# PW_SUPPLY.net
KiCad netlist of a schematic drawn in Altium Designer
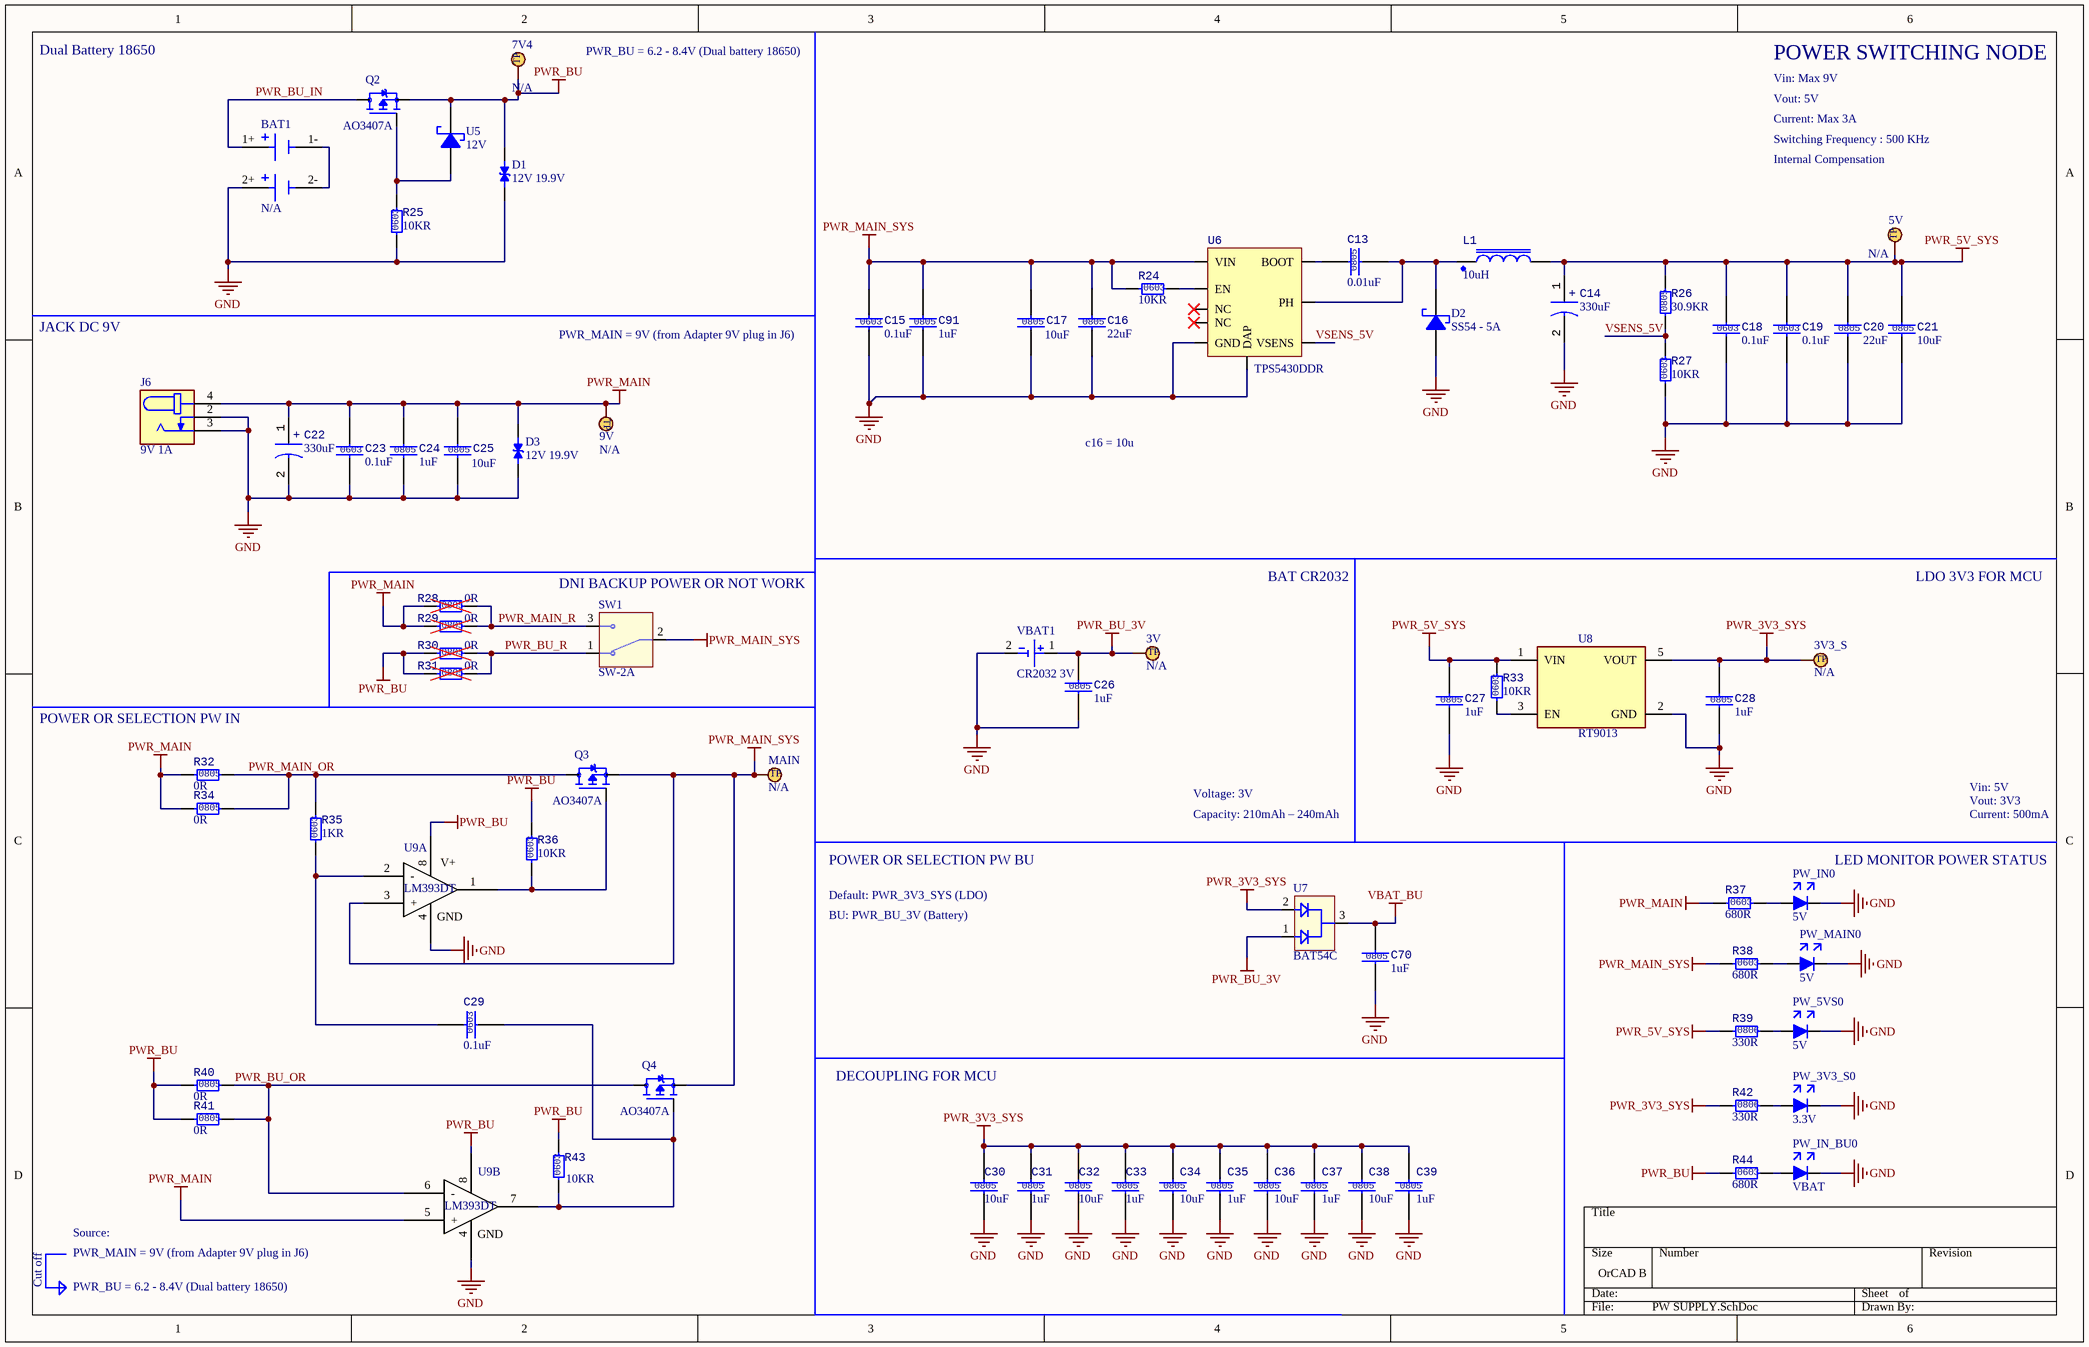
[diagram p0: PW SUPPLY.SchDoc]

(export (version "E")
  (design (tool "Eeschema 10.0.6"))
  (components
    (comp (ref "3V")
      (value "N/A")
      (footprint "Test_point")
      (fields (field (name "Comment") "TEST_POINT"))
      (libsource (lib "Database_Libs1") (part "Test_point"))
    )
    (comp (ref "3V3_S")
      (value "N/A")
      (footprint "Test_point")
      (fields (field (name "Comment") "TEST_POINT"))
      (libsource (lib "Database_Libs1") (part "Test_point"))
    )
    (comp (ref "5V")
      (value "N/A")
      (footprint "Test_point")
      (fields (field (name "Comment") "TEST_POINT"))
      (libsource (lib "Database_Libs1") (part "Test_point"))
    )
    (comp (ref "7V4")
      (value "N/A")
      (footprint "Test_point")
      (fields (field (name "Comment") "TEST_POINT"))
      (libsource (lib "Database_Libs1") (part "Test_point"))
    )
    (comp (ref "9V")
      (value "N/A")
      (footprint "Test_point")
      (fields (field (name "Comment") "TEST_POINT"))
      (libsource (lib "Database_Libs1") (part "Test_point"))
    )
    (comp (ref "BAT1")
      (value "N/A")
      (footprint "Dual_BAT_PCB")
      (description "Dual_Battery_Case_18650")
      (fields (field (name "Comment") "Dual_Battery_Case"))
      (libsource (lib "Database_Libs1") (part "Dual_BAT"))
    )
    (comp (ref "C13")
      (value "0.01uF")
      (footprint "CAPCER 0805 SMD")
      (description "CAPACITOR SMD 0.01uF 50V 10% 0805")
      (fields (field (name "SIZE") "0805") (field (name "TOLERANCE") "10%"))
      (libsource (lib "Database_Libs1") (part "CAPACITOR"))
    )
    (comp (ref "C14")
      (value "330uF")
      (footprint "CAP ALU 6377")
      (description "CAPACITOR ALU SMD 220uF 6.3V 20% 6377")
      (fields (field (name "TOLERANCE") "20%"))
      (libsource (lib "Database_Libs1") (part "CAPACITOR ALU"))
    )
    (comp (ref "C15")
      (value "0.1uF")
      (footprint "CAPCER 0805 SMD")
      (description "CAPACITOR SMD 0.1uF 50V 10% 0603")
      (fields (field (name "SIZE") "0603") (field (name "TOLERANCE") "10%"))
      (libsource (lib "Database_Libs1") (part "CAPACITOR"))
    )
    (comp (ref "C16")
      (value "22uF")
      (footprint "CAPCER 0805 SMD")
      (description "CAPACITOR SMD 22uF 50V 10% 0805")
      (fields (field (name "SIZE") "0805") (field (name "TOLERANCE") "10%"))
      (libsource (lib "Database_Libs1") (part "CAPACITOR"))
    )
    (comp (ref "C17")
      (value "10uF")
      (footprint "CAPCER 0603 SMD")
      (description "CAPACITOR SMD 10uF 25V 10% 0805")
      (fields (field (name "SIZE") "0805") (field (name "TOLERANCE") "10%"))
      (libsource (lib "Database_Libs1") (part "CAPACITOR"))
    )
    (comp (ref "C18")
      (value "0.1uF")
      (footprint "CAPCER 0805 SMD")
      (description "CAPACITOR SMD 0.1uF 50V 10% 0603")
      (fields (field (name "SIZE") "0603") (field (name "TOLERANCE") "10%"))
      (libsource (lib "Database_Libs1") (part "CAPACITOR"))
    )
    (comp (ref "C19")
      (value "0.1uF")
      (footprint "CAPCER 0805 SMD")
      (description "CAPACITOR SMD 0.1uF 50V 10% 0603")
      (fields (field (name "SIZE") "0603") (field (name "TOLERANCE") "10%"))
      (libsource (lib "Database_Libs1") (part "CAPACITOR"))
    )
    (comp (ref "C20")
      (value "22uF")
      (footprint "CAPCER 0805 SMD")
      (description "CAPACITOR SMD 22uF 50V 10% 0805")
      (fields (field (name "SIZE") "0805") (field (name "TOLERANCE") "10%"))
      (libsource (lib "Database_Libs1") (part "CAPACITOR"))
    )
    (comp (ref "C21")
      (value "10uF")
      (footprint "CAPCER 0603 SMD")
      (description "CAPACITOR SMD 10uF 25V 10% 0805")
      (fields (field (name "SIZE") "0805") (field (name "TOLERANCE") "10%"))
      (libsource (lib "Database_Libs1") (part "CAPACITOR"))
    )
    (comp (ref "C22")
      (value "330uF")
      (footprint "CAP ALU 6377")
      (description "CAPACITOR ALU SMD 220uF 6.3V 20% 6377")
      (fields (field (name "TOLERANCE") "20%"))
      (libsource (lib "Database_Libs1") (part "CAPACITOR ALU"))
    )
    (comp (ref "C23")
      (value "0.1uF")
      (footprint "CAPCER 0805 SMD")
      (description "CAPACITOR SMD 0.1uF 50V 10% 0603")
      (fields (field (name "SIZE") "0603") (field (name "TOLERANCE") "10%"))
      (libsource (lib "Database_Libs1") (part "CAPACITOR"))
    )
    (comp (ref "C24")
      (value "1uF")
      (footprint "CAPCER 0805 SMD")
      (description "CAPACITOR SMD 1uF 16V 10% 0805")
      (fields (field (name "SIZE") "0805") (field (name "TOLERANCE") "10%"))
      (libsource (lib "Database_Libs1") (part "CAPACITOR"))
    )
    (comp (ref "C25")
      (value "10uF")
      (footprint "CAPCER 0603 SMD")
      (description "CAPACITOR SMD 10uF 25V 10% 0805")
      (fields (field (name "SIZE") "0805") (field (name "TOLERANCE") "10%"))
      (libsource (lib "Database_Libs1") (part "CAPACITOR"))
    )
    (comp (ref "C26")
      (value "1uF")
      (footprint "CAPCER 0805 SMD")
      (description "CAPACITOR SMD 1uF 16V 10% 0805")
      (fields (field (name "SIZE") "0805") (field (name "TOLERANCE") "10%"))
      (libsource (lib "Database_Libs1") (part "CAPACITOR"))
    )
    (comp (ref "C27")
      (value "1uF")
      (footprint "CAPCER 0805 SMD")
      (description "CAPACITOR SMD 1uF 16V 10% 0805")
      (fields (field (name "SIZE") "0805") (field (name "TOLERANCE") "10%"))
      (libsource (lib "Database_Libs1") (part "CAPACITOR"))
    )
    (comp (ref "C28")
      (value "1uF")
      (footprint "CAPCER 0805 SMD")
      (description "CAPACITOR SMD 1uF 16V 10% 0805")
      (fields (field (name "SIZE") "0805") (field (name "TOLERANCE") "10%"))
      (libsource (lib "Database_Libs1") (part "CAPACITOR"))
    )
    (comp (ref "C29")
      (value "0.1uF")
      (footprint "CAPCER 0805 SMD")
      (description "CAPACITOR SMD 0.1uF 50V 10% 0603")
      (fields (field (name "SIZE") "0603") (field (name "TOLERANCE") "10%"))
      (libsource (lib "Database_Libs1") (part "CAPACITOR"))
    )
    (comp (ref "C30")
      (value "10uF")
      (footprint "CAPCER 0603 SMD")
      (description "CAPACITOR SMD 10uF 25V 10% 0805")
      (fields (field (name "SIZE") "0805") (field (name "TOLERANCE") "10%"))
      (libsource (lib "Database_Libs1") (part "CAPACITOR"))
    )
    (comp (ref "C31")
      (value "1uF")
      (footprint "CAPCER 0805 SMD")
      (description "CAPACITOR SMD 1uF 16V 10% 0805")
      (fields (field (name "SIZE") "0805") (field (name "TOLERANCE") "10%"))
      (libsource (lib "Database_Libs1") (part "CAPACITOR"))
    )
    (comp (ref "C32")
      (value "10uF")
      (footprint "CAPCER 0603 SMD")
      (description "CAPACITOR SMD 10uF 25V 10% 0805")
      (fields (field (name "SIZE") "0805") (field (name "TOLERANCE") "10%"))
      (libsource (lib "Database_Libs1") (part "CAPACITOR"))
    )
    (comp (ref "C33")
      (value "1uF")
      (footprint "CAPCER 0805 SMD")
      (description "CAPACITOR SMD 1uF 16V 10% 0805")
      (fields (field (name "SIZE") "0805") (field (name "TOLERANCE") "10%"))
      (libsource (lib "Database_Libs1") (part "CAPACITOR"))
    )
    (comp (ref "C34")
      (value "10uF")
      (footprint "CAPCER 0603 SMD")
      (description "CAPACITOR SMD 10uF 25V 10% 0805")
      (fields (field (name "SIZE") "0805") (field (name "TOLERANCE") "10%"))
      (libsource (lib "Database_Libs1") (part "CAPACITOR"))
    )
    (comp (ref "C35")
      (value "1uF")
      (footprint "CAPCER 0805 SMD")
      (description "CAPACITOR SMD 1uF 16V 10% 0805")
      (fields (field (name "SIZE") "0805") (field (name "TOLERANCE") "10%"))
      (libsource (lib "Database_Libs1") (part "CAPACITOR"))
    )
    (comp (ref "C36")
      (value "10uF")
      (footprint "CAPCER 0603 SMD")
      (description "CAPACITOR SMD 10uF 25V 10% 0805")
      (fields (field (name "SIZE") "0805") (field (name "TOLERANCE") "10%"))
      (libsource (lib "Database_Libs1") (part "CAPACITOR"))
    )
    (comp (ref "C37")
      (value "1uF")
      (footprint "CAPCER 0805 SMD")
      (description "CAPACITOR SMD 1uF 16V 10% 0805")
      (fields (field (name "SIZE") "0805") (field (name "TOLERANCE") "10%"))
      (libsource (lib "Database_Libs1") (part "CAPACITOR"))
    )
    (comp (ref "C38")
      (value "10uF")
      (footprint "CAPCER 0603 SMD")
      (description "CAPACITOR SMD 10uF 25V 10% 0805")
      (fields (field (name "SIZE") "0805") (field (name "TOLERANCE") "10%"))
      (libsource (lib "Database_Libs1") (part "CAPACITOR"))
    )
    (comp (ref "C39")
      (value "1uF")
      (footprint "CAPCER 0805 SMD")
      (description "CAPACITOR SMD 1uF 16V 10% 0805")
      (fields (field (name "SIZE") "0805") (field (name "TOLERANCE") "10%"))
      (libsource (lib "Database_Libs1") (part "CAPACITOR"))
    )
    (comp (ref "C70")
      (value "1uF")
      (footprint "CAPCER 0805 SMD")
      (description "CAPACITOR SMD 1uF 16V 10% 0805")
      (fields (field (name "SIZE") "0805") (field (name "TOLERANCE") "10%"))
      (libsource (lib "Database_Libs1") (part "CAPACITOR"))
    )
    (comp (ref "C91")
      (value "1uF")
      (footprint "CAPCER 0805 SMD")
      (description "CAPACITOR SMD 1uF 16V 10% 0805")
      (fields (field (name "SIZE") "0805") (field (name "TOLERANCE") "10%"))
      (libsource (lib "Database_Libs1") (part "CAPACITOR"))
    )
    (comp (ref "D1")
      (value "12V 19.9V")
      (footprint "DO-214AC")
      (description "TVS DIODE 12V 19.9V DO214AC")
      (fields (field (name "Comment") "SMAJ12A"))
      (libsource (lib "Database_Libs1") (part "SMAJ12"))
    )
    (comp (ref "D2")
      (value "SS54 - 5A")
      (footprint "DO-214AC")
      (fields (field (name "Comment") "SS54"))
      (libsource (lib "Database_Libs2") (part "DIODE_ZE"))
    )
    (comp (ref "D3")
      (value "12V 19.9V")
      (footprint "DO-214AC")
      (description "TVS DIODE 12V 19.9V DO214AC")
      (fields (field (name "Comment") "SMAJ12A"))
      (libsource (lib "Database_Libs1") (part "SMAJ12"))
    )
    (comp (ref "J6")
      (value "9V 1A")
      (footprint "PW_JACK_DC_5525")
      (libsource (lib "Database_Libs2") (part "JACK 2.1"))
    )
    (comp (ref "L1")
      (value "10uH")
      (footprint "IND_8D43")
      (libsource (lib "Database_Libs2") (part "INDUCTOR"))
    )
    (comp (ref "MAIN")
      (value "N/A")
      (footprint "Test_point")
      (fields (field (name "Comment") "TEST_POINT"))
      (libsource (lib "Database_Libs1") (part "Test_point"))
    )
    (comp (ref "PW_3V3_S0")
      (value "3.3V")
      (footprint "LED 0805 SMD")
      (description "Size 2x1.2mm, điện áp 1.8-2.6VDC")
      (fields (field (name "Comment") "LED_RED"))
      (libsource (lib "Database_Libs1") (part "LED_RED"))
    )
    (comp (ref "PW_5VS0")
      (value "5V")
      (footprint "LED 0805 SMD")
      (description "Size 2x1.2mm, điện áp 1.8-2.6VDC")
      (fields (field (name "Comment") "LED_RED"))
      (libsource (lib "Database_Libs1") (part "LED_RED"))
    )
    (comp (ref "PW_IN0")
      (value "5V")
      (footprint "LED 0805 SMD")
      (description "Size 2x1.2mm, điện áp 1.8-2.6VDC")
      (fields (field (name "Comment") "LED_RED"))
      (libsource (lib "Database_Libs1") (part "LED_RED"))
    )
    (comp (ref "PW_IN_BU0")
      (value "VBAT")
      (footprint "LED 0805 SMD")
      (description "Size 2x1.2mm, điện áp 1.8-2.6VDC")
      (fields (field (name "Comment") "LED_RED"))
      (libsource (lib "Database_Libs1") (part "LED_RED"))
    )
    (comp (ref "PW_MAIN0")
      (value "5V")
      (footprint "LED 0805 SMD")
      (description "Size 2x1.2mm, điện áp 1.8-2.6VDC")
      (fields (field (name "Comment") "LED_RED"))
      (libsource (lib "Database_Libs1") (part "LED_RED"))
    )
    (comp (ref "Q2")
      (value "AO3407A")
      (footprint "SOT23-3")
      (description "AO3407A MOSFET Kênh P 30V 4.3A SOT-23-3")
      (libsource (lib "Database_Libs1") (part "P_MOS"))
    )
    (comp (ref "Q3")
      (value "AO3407A")
      (footprint "SOT23-3")
      (description "AO3407A MOSFET Kênh P 30V 4.3A SOT-23-3")
      (libsource (lib "Database_Libs1") (part "P_MOS"))
    )
    (comp (ref "Q4")
      (value "AO3407A")
      (footprint "SOT23-3")
      (description "AO3407A MOSFET Kênh P 30V 4.3A SOT-23-3")
      (libsource (lib "Database_Libs1") (part "P_MOS"))
    )
    (comp (ref "R24")
      (value "10KR")
      (footprint "RESC 0603(1608) SMD")
      (description "RESISTOR SMD 10KR OHM 1% 100mW 0603")
      (fields (field (name "SIZE") "0603") (field (name "TOLERANCE") "1%"))
      (libsource (lib "") (part "RESISTOR_1"))
    )
    (comp (ref "R25")
      (value "10KR")
      (footprint "RESC 0603(1608) SMD")
      (description "RESISTOR SMD 10KR OHM 1% 100mW 0603")
      (fields (field (name "SIZE") "0603") (field (name "TOLERANCE") "1%"))
      (libsource (lib "Database_Libs1") (part "RESISTOR"))
    )
    (comp (ref "R26")
      (value "30.9KR")
      (footprint "RESC 0805 SMD")
      (description "Điện Trở 30.9 KOhm 0805 1%")
      (fields (field (name "SIZE") "0805"))
      (libsource (lib "") (part "RESISTOR_1"))
    )
    (comp (ref "R27")
      (value "10KR")
      (footprint "RESC 0603(1608) SMD")
      (description "RESISTOR SMD 10KR OHM 1% 100mW 0603")
      (fields (field (name "SIZE") "0603") (field (name "TOLERANCE") "1%"))
      (libsource (lib "Database_Libs1") (part "RESISTOR"))
    )
    (comp (ref "R28")
      (value "0R")
      (footprint "RESC 0805 SMD")
      (fields (field (name "SIZE") "0805"))
      (libsource (lib "Database_Libs2") (part "RESISTOR"))
    )
    (comp (ref "R29")
      (value "0R")
      (footprint "RESC 0805 SMD")
      (fields (field (name "SIZE") "0805"))
      (libsource (lib "Database_Libs2") (part "RESISTOR"))
    )
    (comp (ref "R30")
      (value "0R")
      (footprint "RESC 0805 SMD")
      (fields (field (name "SIZE") "0805"))
      (libsource (lib "Database_Libs2") (part "RESISTOR"))
    )
    (comp (ref "R31")
      (value "0R")
      (footprint "RESC 0805 SMD")
      (fields (field (name "SIZE") "0805"))
      (libsource (lib "Database_Libs2") (part "RESISTOR"))
    )
    (comp (ref "R32")
      (value "0R")
      (footprint "RESC 0805 SMD")
      (fields (field (name "SIZE") "0805"))
      (libsource (lib "Database_Libs2") (part "RESISTOR"))
    )
    (comp (ref "R33")
      (value "10KR")
      (footprint "RESC 0603(1608) SMD")
      (description "RESISTOR SMD 10KR OHM 1% 100mW 0603")
      (fields (field (name "SIZE") "0603") (field (name "TOLERANCE") "1%"))
      (libsource (lib "Database_Libs1") (part "RESISTOR"))
    )
    (comp (ref "R34")
      (value "0R")
      (footprint "RESC 0805 SMD")
      (fields (field (name "SIZE") "0805"))
      (libsource (lib "Database_Libs2") (part "RESISTOR"))
    )
    (comp (ref "R35")
      (value "1KR")
      (footprint "RESC 0603(1608) SMD")
      (description "RESISTOR SMD 1KR OHM 1% 100mW 0603")
      (fields (field (name "SIZE") "0603") (field (name "TOLERANCE") "1%"))
      (libsource (lib "Database_Libs1") (part "RESISTOR"))
    )
    (comp (ref "R36")
      (value "10KR")
      (footprint "RESC 0603(1608) SMD")
      (description "RESISTOR SMD 10KR OHM 1% 100mW 0603")
      (fields (field (name "SIZE") "0603") (field (name "TOLERANCE") "1%"))
      (libsource (lib "Database_Libs1") (part "RESISTOR"))
    )
    (comp (ref "R37")
      (value "680R")
      (footprint "RESC 0603(1608) SMD")
      (description "RESISTOR SMD 680R OHM 5% 100mW 0603")
      (fields (field (name "SIZE") "0603") (field (name "TOLERANCE") "5%"))
      (libsource (lib "") (part "RESISTOR_1"))
    )
    (comp (ref "R38")
      (value "680R")
      (footprint "RESC 0603(1608) SMD")
      (description "RESISTOR SMD 680R OHM 5% 100mW 0603")
      (fields (field (name "SIZE") "0603") (field (name "TOLERANCE") "5%"))
      (libsource (lib "") (part "RESISTOR_1"))
    )
    (comp (ref "R39")
      (value "330R")
      (footprint "RESC 0805 SMD")
      (description "RESISTOR SMD 330R OHM 1% 125mW 0805")
      (fields (field (name "SIZE") "0806") (field (name "TOLERANCE") "1%"))
      (libsource (lib "") (part "RESISTOR_1"))
    )
    (comp (ref "R40")
      (value "0R")
      (footprint "RESC 0805 SMD")
      (fields (field (name "SIZE") "0805"))
      (libsource (lib "Database_Libs2") (part "RESISTOR"))
    )
    (comp (ref "R41")
      (value "0R")
      (footprint "RESC 0805 SMD")
      (fields (field (name "SIZE") "0805"))
      (libsource (lib "Database_Libs2") (part "RESISTOR"))
    )
    (comp (ref "R42")
      (value "330R")
      (footprint "RESC 0805 SMD")
      (description "RESISTOR SMD 330R OHM 1% 125mW 0805")
      (fields (field (name "SIZE") "0806") (field (name "TOLERANCE") "1%"))
      (libsource (lib "") (part "RESISTOR_1"))
    )
    (comp (ref "R43")
      (value "10KR")
      (footprint "RESC 0603(1608) SMD")
      (description "RESISTOR SMD 10KR OHM 1% 100mW 0603")
      (fields (field (name "SIZE") "0603") (field (name "TOLERANCE") "1%"))
      (libsource (lib "Database_Libs1") (part "RESISTOR"))
    )
    (comp (ref "R44")
      (value "680R")
      (footprint "RESC 0603(1608) SMD")
      (description "RESISTOR SMD 680R OHM 5% 100mW 0603")
      (fields (field (name "SIZE") "0603") (field (name "TOLERANCE") "5%"))
      (libsource (lib "") (part "RESISTOR_1"))
    )
    (comp (ref "SW1")
      (value "SW-2A")
      (footprint "SLIDE-SW")
      (description "SS-12F23G4 Công Tắc Trượt 5 Chân Xuyên Lỗ ON-OFF Chỉnh Ngang 1P2T 2A")
      (fields (field (name "Comment") "SW 2A"))
      (libsource (lib "Database_Libs1") (part "SLIDE-SW"))
    )
    (comp (ref "U5")
      (value "12V")
      (footprint "SOD-123F")
      (description "BZT52H-C12 Diode Zener 12V 375mW SOD-123F")
      (fields (field (name "TOLERANCE") "5%") (field (name "Comment") "BZT52H"))
      (libsource (lib "Database_Libs1") (part "DIODE_ZE"))
    )
    (comp (ref "U6")
      (value "TPS5430DDR")
      (footprint "8-SOIC")
      (description "TPS543x 3A, Wide Input Range, Step-Down Converter")
      (fields (field (name "Comment") "TPS5430DDAR"))
      (libsource (lib "Database_Libs1") (part "TPS5430DDA"))
    )
    (comp (ref "U7")
      (value "BAT54C")
      (footprint "SOT23-3")
      (description "DIODE ARRAY SCHOTTKY 30V SOT23-3")
      (libsource (lib "Database_Libs2") (part "BAT54C"))
    )
    (comp (ref "U8")
      (value "RT9013")
      (footprint "SOT-23-5")
      (description "IC REG LINEAR 3.3V 500MA SOT23-5")
      (libsource (lib "Database_Libs1") (part "RT9013"))
    )
    (comp (ref "U9")
      (value "LM393DT")
      (footprint "8-SOIC-OPA")
      (libsource (lib "Database_Libs2") (part "LM393DT"))
    )
    (comp (ref "VBAT1")
      (value "CR2032 3V")
      (footprint "HOLDER BAT")
      (description "BS-6 Đế Pin CR2032 CR2025 Dán SMD")
      (fields (field (name "Comment") "HOL CR2032"))
      (libsource (lib "Database_Libs1") (part "HOLDER BAT"))
    )
  )
  (nets
    (net (code "1") (name "/PWR_BU_IN") (class "Default")
      (node (ref "BAT1") (pin "1+") (pinfunction "1+_1+") (pintype "passive"))
      (node (ref "Q2") (pin "3") (pinfunction "D_3") (pintype "passive"))
    )
    (net (code "2") (name "/PWR_BU_OR") (class "Default")
      (node (ref "Q4") (pin "3") (pinfunction "D_3") (pintype "passive"))
      (node (ref "R40") (pin "2") (pinfunction "2_2") (pintype "passive"))
      (node (ref "R41") (pin "2") (pinfunction "2_2") (pintype "passive"))
      (node (ref "U9") (pin "6") (pinfunction "-_6") (pintype "passive"))
    )
    (net (code "3") (name "/PWR_BU_R") (class "Default")
      (node (ref "R30") (pin "2") (pinfunction "2_2") (pintype "passive"))
      (node (ref "R31") (pin "2") (pinfunction "2_2") (pintype "passive"))
      (node (ref "SW1") (pin "1") (pinfunction "1_1") (pintype "passive"))
    )
    (net (code "4") (name "/PWR_MAIN_OR") (class "Default")
      (node (ref "Q3") (pin "3") (pinfunction "D_3") (pintype "passive"))
      (node (ref "R32") (pin "2") (pinfunction "2_2") (pintype "passive"))
      (node (ref "R34") (pin "2") (pinfunction "2_2") (pintype "passive"))
      (node (ref "R35") (pin "2") (pinfunction "2_2") (pintype "passive"))
    )
    (net (code "5") (name "/PWR_MAIN_R") (class "Default")
      (node (ref "R28") (pin "2") (pinfunction "2_2") (pintype "passive"))
      (node (ref "R29") (pin "2") (pinfunction "2_2") (pintype "passive"))
      (node (ref "SW1") (pin "3") (pinfunction "3_3") (pintype "passive"))
    )
    (net (code "6") (name "/VSENS_5V") (class "Default")
      (node (ref "R26") (pin "1") (pinfunction "1_1") (pintype "passive"))
      (node (ref "R27") (pin "2") (pinfunction "2_2") (pintype "passive"))
      (node (ref "U6") (pin "4") (pinfunction "VSENS_4") (pintype "passive"))
    )
    (net (code "7") (name "GND") (class "Default")
      (node (ref "BAT1") (pin "2+") (pinfunction "2+_2+") (pintype "passive"))
      (node (ref "C14") (pin "2") (pinfunction "2_2") (pintype "passive"))
      (node (ref "C15") (pin "2") (pinfunction "2_2") (pintype "passive"))
      (node (ref "C16") (pin "2") (pinfunction "2_2") (pintype "passive"))
      (node (ref "C17") (pin "2") (pinfunction "2_2") (pintype "passive"))
      (node (ref "C18") (pin "2") (pinfunction "2_2") (pintype "passive"))
      (node (ref "C19") (pin "2") (pinfunction "2_2") (pintype "passive"))
      (node (ref "C20") (pin "2") (pinfunction "2_2") (pintype "passive"))
      (node (ref "C21") (pin "2") (pinfunction "2_2") (pintype "passive"))
      (node (ref "C22") (pin "2") (pinfunction "2_2") (pintype "passive"))
      (node (ref "C23") (pin "2") (pinfunction "2_2") (pintype "passive"))
      (node (ref "C24") (pin "2") (pinfunction "2_2") (pintype "passive"))
      (node (ref "C25") (pin "2") (pinfunction "2_2") (pintype "passive"))
      (node (ref "C26") (pin "2") (pinfunction "2_2") (pintype "passive"))
      (node (ref "C27") (pin "2") (pinfunction "2_2") (pintype "passive"))
      (node (ref "C28") (pin "2") (pinfunction "2_2") (pintype "passive"))
      (node (ref "C30") (pin "2") (pinfunction "2_2") (pintype "passive"))
      (node (ref "C31") (pin "2") (pinfunction "2_2") (pintype "passive"))
      (node (ref "C32") (pin "2") (pinfunction "2_2") (pintype "passive"))
      (node (ref "C33") (pin "2") (pinfunction "2_2") (pintype "passive"))
      (node (ref "C34") (pin "2") (pinfunction "2_2") (pintype "passive"))
      (node (ref "C35") (pin "2") (pinfunction "2_2") (pintype "passive"))
      (node (ref "C36") (pin "2") (pinfunction "2_2") (pintype "passive"))
      (node (ref "C37") (pin "2") (pinfunction "2_2") (pintype "passive"))
      (node (ref "C38") (pin "2") (pinfunction "2_2") (pintype "passive"))
      (node (ref "C39") (pin "2") (pinfunction "2_2") (pintype "passive"))
      (node (ref "C70") (pin "2") (pinfunction "2_2") (pintype "passive"))
      (node (ref "C91") (pin "2") (pinfunction "2_2") (pintype "passive"))
      (node (ref "D1") (pin "1") (pinfunction "1_1") (pintype "passive"))
      (node (ref "D2") (pin "1") (pinfunction "A_1") (pintype "passive"))
      (node (ref "D3") (pin "1") (pinfunction "1_1") (pintype "passive"))
      (node (ref "J6") (pin "2") (pinfunction "4_2") (pintype "passive"))
      (node (ref "J6") (pin "3") (pinfunction "5_3") (pintype "passive"))
      (node (ref "PW_3V3_S0") (pin "C") (pinfunction "K_C") (pintype "passive"))
      (node (ref "PW_5VS0") (pin "C") (pinfunction "K_C") (pintype "passive"))
      (node (ref "PW_IN0") (pin "C") (pinfunction "K_C") (pintype "passive"))
      (node (ref "PW_IN_BU0") (pin "C") (pinfunction "K_C") (pintype "passive"))
      (node (ref "PW_MAIN0") (pin "C") (pinfunction "K_C") (pintype "passive"))
      (node (ref "R25") (pin "1") (pinfunction "1_1") (pintype "passive"))
      (node (ref "R27") (pin "1") (pinfunction "1_1") (pintype "passive"))
      (node (ref "U6") (pin "6") (pinfunction "GND_6") (pintype "passive"))
      (node (ref "U6") (pin "9") (pinfunction "DAP_9") (pintype "passive"))
      (node (ref "U8") (pin "2") (pinfunction "GND_2") (pintype "power_in"))
      (node (ref "U9") (pin "4") (pinfunction "GND_4") (pintype "passive"))
      (node (ref "VBAT1") (pin "2") (pinfunction "NEG_2") (pintype "passive"))
    )
    (net (code "8") (name "Net-(BAT1-Pad1-)") (class "Default")
      (node (ref "BAT1") (pin "1-") (pinfunction "1-_1-") (pintype "passive"))
      (node (ref "BAT1") (pin "2-") (pinfunction "2-_2-") (pintype "passive"))
    )
    (net (code "9") (name "Net-(D2-K)") (class "Default")
      (node (ref "C13") (pin "2") (pinfunction "2_2") (pintype "passive"))
      (node (ref "D2") (pin "2") (pinfunction "K_2") (pintype "passive"))
      (node (ref "L1") (pin "1") (pinfunction "1_1") (pintype "passive"))
      (node (ref "U6") (pin "8") (pinfunction "PH_8") (pintype "passive"))
    )
    (net (code "10") (name "Net-(PW_3V3_S0-PadA)") (class "Default")
      (node (ref "PW_3V3_S0") (pin "A") (pinfunction "A_A") (pintype "passive"))
      (node (ref "R42") (pin "2") (pinfunction "2_2") (pintype "passive"))
    )
    (net (code "11") (name "Net-(PW_5VS0-PadA)") (class "Default")
      (node (ref "PW_5VS0") (pin "A") (pinfunction "A_A") (pintype "passive"))
      (node (ref "R39") (pin "2") (pinfunction "2_2") (pintype "passive"))
    )
    (net (code "12") (name "Net-(PW_IN0-PadA)") (class "Default")
      (node (ref "PW_IN0") (pin "A") (pinfunction "A_A") (pintype "passive"))
      (node (ref "R37") (pin "2") (pinfunction "2_2") (pintype "passive"))
    )
    (net (code "13") (name "Net-(PW_IN_BU0-PadA)") (class "Default")
      (node (ref "PW_IN_BU0") (pin "A") (pinfunction "A_A") (pintype "passive"))
      (node (ref "R44") (pin "2") (pinfunction "2_2") (pintype "passive"))
    )
    (net (code "14") (name "Net-(PW_MAIN0-PadA)") (class "Default")
      (node (ref "PW_MAIN0") (pin "A") (pinfunction "A_A") (pintype "passive"))
      (node (ref "R38") (pin "2") (pinfunction "2_2") (pintype "passive"))
    )
    (net (code "15") (name "Net-(Q2-G)") (class "Default")
      (node (ref "Q2") (pin "1") (pinfunction "G_1") (pintype "passive"))
      (node (ref "R25") (pin "2") (pinfunction "2_2") (pintype "passive"))
      (node (ref "U5") (pin "1") (pinfunction "A_1") (pintype "passive"))
    )
    (net (code "16") (name "Net-(Q3-G)") (class "Default")
      (node (ref "Q3") (pin "1") (pinfunction "G_1") (pintype "passive"))
      (node (ref "R36") (pin "1") (pinfunction "1_1") (pintype "passive"))
      (node (ref "U9") (pin "1") (pinfunction "OUT_1_1") (pintype "passive"))
    )
    (net (code "17") (name "Net-(Q4-G)") (class "Default")
      (node (ref "C29") (pin "2") (pinfunction "2_2") (pintype "passive"))
      (node (ref "Q4") (pin "1") (pinfunction "G_1") (pintype "passive"))
      (node (ref "R43") (pin "1") (pinfunction "1_1") (pintype "passive"))
      (node (ref "U9") (pin "7") (pinfunction "OUT_2_7") (pintype "passive"))
    )
    (net (code "18") (name "Net-(U6-BOOT)") (class "Default")
      (node (ref "C13") (pin "1") (pinfunction "1_1") (pintype "passive"))
      (node (ref "U6") (pin "1") (pinfunction "BOOT_1") (pintype "passive"))
    )
    (net (code "19") (name "Net-(U6-EN)") (class "Default")
      (node (ref "R24") (pin "2") (pinfunction "2_2") (pintype "passive"))
      (node (ref "U6") (pin "5") (pinfunction "EN_5") (pintype "passive"))
    )
    (net (code "20") (name "Net-(U8-EN)") (class "Default")
      (node (ref "R33") (pin "1") (pinfunction "1_1") (pintype "passive"))
      (node (ref "U8") (pin "3") (pinfunction "EN_3") (pintype "passive"))
    )
    (net (code "21") (name "Net-(U9A--)") (class "Default")
      (node (ref "C29") (pin "1") (pinfunction "1_1") (pintype "passive"))
      (node (ref "R35") (pin "1") (pinfunction "1_1") (pintype "passive"))
      (node (ref "U9") (pin "2") (pinfunction "-_2") (pintype "passive"))
    )
    (net (code "22") (name "PWR_3V3_SYS") (class "Default")
      (node (ref "3V3_S") (pin "1") (pinfunction "1_1") (pintype "passive"))
      (node (ref "C28") (pin "1") (pinfunction "1_1") (pintype "passive"))
      (node (ref "C30") (pin "1") (pinfunction "1_1") (pintype "passive"))
      (node (ref "C31") (pin "1") (pinfunction "1_1") (pintype "passive"))
      (node (ref "C32") (pin "1") (pinfunction "1_1") (pintype "passive"))
      (node (ref "C33") (pin "1") (pinfunction "1_1") (pintype "passive"))
      (node (ref "C34") (pin "1") (pinfunction "1_1") (pintype "passive"))
      (node (ref "C35") (pin "1") (pinfunction "1_1") (pintype "passive"))
      (node (ref "C36") (pin "1") (pinfunction "1_1") (pintype "passive"))
      (node (ref "C37") (pin "1") (pinfunction "1_1") (pintype "passive"))
      (node (ref "C38") (pin "1") (pinfunction "1_1") (pintype "passive"))
      (node (ref "C39") (pin "1") (pinfunction "1_1") (pintype "passive"))
      (node (ref "R42") (pin "1") (pinfunction "1_1") (pintype "passive"))
      (node (ref "U7") (pin "2") (pinfunction "2_2") (pintype "passive"))
      (node (ref "U8") (pin "5") (pinfunction "VOUT_5") (pintype "passive"))
    )
    (net (code "23") (name "PWR_5V_SYS") (class "Default")
      (node (ref "5V") (pin "1") (pinfunction "1_1") (pintype "passive"))
      (node (ref "C14") (pin "1") (pinfunction "1_1") (pintype "passive"))
      (node (ref "C18") (pin "1") (pinfunction "1_1") (pintype "passive"))
      (node (ref "C19") (pin "1") (pinfunction "1_1") (pintype "passive"))
      (node (ref "C20") (pin "1") (pinfunction "1_1") (pintype "passive"))
      (node (ref "C21") (pin "1") (pinfunction "1_1") (pintype "passive"))
      (node (ref "C27") (pin "1") (pinfunction "1_1") (pintype "passive"))
      (node (ref "L1") (pin "2") (pinfunction "2_2") (pintype "passive"))
      (node (ref "R26") (pin "2") (pinfunction "2_2") (pintype "passive"))
      (node (ref "R33") (pin "2") (pinfunction "2_2") (pintype "passive"))
      (node (ref "R39") (pin "1") (pinfunction "1_1") (pintype "passive"))
      (node (ref "U8") (pin "1") (pinfunction "VIN_1") (pintype "power_in"))
    )
    (net (code "24") (name "PWR_BU") (class "Default")
      (node (ref "7V4") (pin "1") (pinfunction "1_1") (pintype "passive"))
      (node (ref "D1") (pin "2") (pinfunction "2_2") (pintype "passive"))
      (node (ref "Q2") (pin "2") (pinfunction "S_2") (pintype "passive"))
      (node (ref "R30") (pin "1") (pinfunction "1_1") (pintype "passive"))
      (node (ref "R31") (pin "1") (pinfunction "1_1") (pintype "passive"))
      (node (ref "R36") (pin "2") (pinfunction "2_2") (pintype "passive"))
      (node (ref "R40") (pin "1") (pinfunction "1_1") (pintype "passive"))
      (node (ref "R41") (pin "1") (pinfunction "1_1") (pintype "passive"))
      (node (ref "R43") (pin "2") (pinfunction "2_2") (pintype "passive"))
      (node (ref "R44") (pin "1") (pinfunction "1_1") (pintype "passive"))
      (node (ref "U5") (pin "2") (pinfunction "K_2") (pintype "passive"))
      (node (ref "U9") (pin "8") (pinfunction "VCC_8") (pintype "passive"))
    )
    (net (code "25") (name "PWR_BU_3V") (class "Default")
      (node (ref "3V") (pin "1") (pinfunction "1_1") (pintype "passive"))
      (node (ref "C26") (pin "1") (pinfunction "1_1") (pintype "passive"))
      (node (ref "U7") (pin "1") (pinfunction "1_1") (pintype "passive"))
      (node (ref "VBAT1") (pin "1") (pinfunction "POS_1") (pintype "passive"))
    )
    (net (code "26") (name "PWR_MAIN") (class "Default")
      (node (ref "9V") (pin "1") (pinfunction "1_1") (pintype "passive"))
      (node (ref "C22") (pin "1") (pinfunction "1_1") (pintype "passive"))
      (node (ref "C23") (pin "1") (pinfunction "1_1") (pintype "passive"))
      (node (ref "C24") (pin "1") (pinfunction "1_1") (pintype "passive"))
      (node (ref "C25") (pin "1") (pinfunction "1_1") (pintype "passive"))
      (node (ref "D3") (pin "2") (pinfunction "2_2") (pintype "passive"))
      (node (ref "J6") (pin "4") (pinfunction "2_4") (pintype "passive"))
      (node (ref "R28") (pin "1") (pinfunction "1_1") (pintype "passive"))
      (node (ref "R29") (pin "1") (pinfunction "1_1") (pintype "passive"))
      (node (ref "R32") (pin "1") (pinfunction "1_1") (pintype "passive"))
      (node (ref "R34") (pin "1") (pinfunction "1_1") (pintype "passive"))
      (node (ref "R37") (pin "1") (pinfunction "1_1") (pintype "passive"))
      (node (ref "U9") (pin "5") (pinfunction "+_5") (pintype "passive"))
    )
    (net (code "27") (name "PWR_MAIN_SYS") (class "Default")
      (node (ref "C15") (pin "1") (pinfunction "1_1") (pintype "passive"))
      (node (ref "C16") (pin "1") (pinfunction "1_1") (pintype "passive"))
      (node (ref "C17") (pin "1") (pinfunction "1_1") (pintype "passive"))
      (node (ref "C91") (pin "1") (pinfunction "1_1") (pintype "passive"))
      (node (ref "MAIN") (pin "1") (pinfunction "1_1") (pintype "passive"))
      (node (ref "Q3") (pin "2") (pinfunction "S_2") (pintype "passive"))
      (node (ref "Q4") (pin "2") (pinfunction "S_2") (pintype "passive"))
      (node (ref "R24") (pin "1") (pinfunction "1_1") (pintype "passive"))
      (node (ref "R38") (pin "1") (pinfunction "1_1") (pintype "passive"))
      (node (ref "SW1") (pin "2") (pinfunction "2_2") (pintype "passive"))
      (node (ref "U6") (pin "7") (pinfunction "VIN_7") (pintype "passive"))
      (node (ref "U9") (pin "3") (pinfunction "+_3") (pintype "passive"))
    )
    (net (code "28") (name "VBAT_BU") (class "Default")
      (node (ref "C70") (pin "1") (pinfunction "1_1") (pintype "passive"))
      (node (ref "U7") (pin "3") (pinfunction "3_3") (pintype "passive"))
    )
    (net (code "29") (name "unconnected-(U6-NC-Pad2)") (class "Default")
      (node (ref "U6") (pin "2") (pinfunction "NC_2") (pintype "passive+no_connect"))
    )
    (net (code "30") (name "unconnected-(U6-NC-Pad3)") (class "Default")
      (node (ref "U6") (pin "3") (pinfunction "NC_3") (pintype "passive+no_connect"))
    )
  )
)
